# air_pod_case.net
KiCad netlist of a schematic drawn in Altium Designer
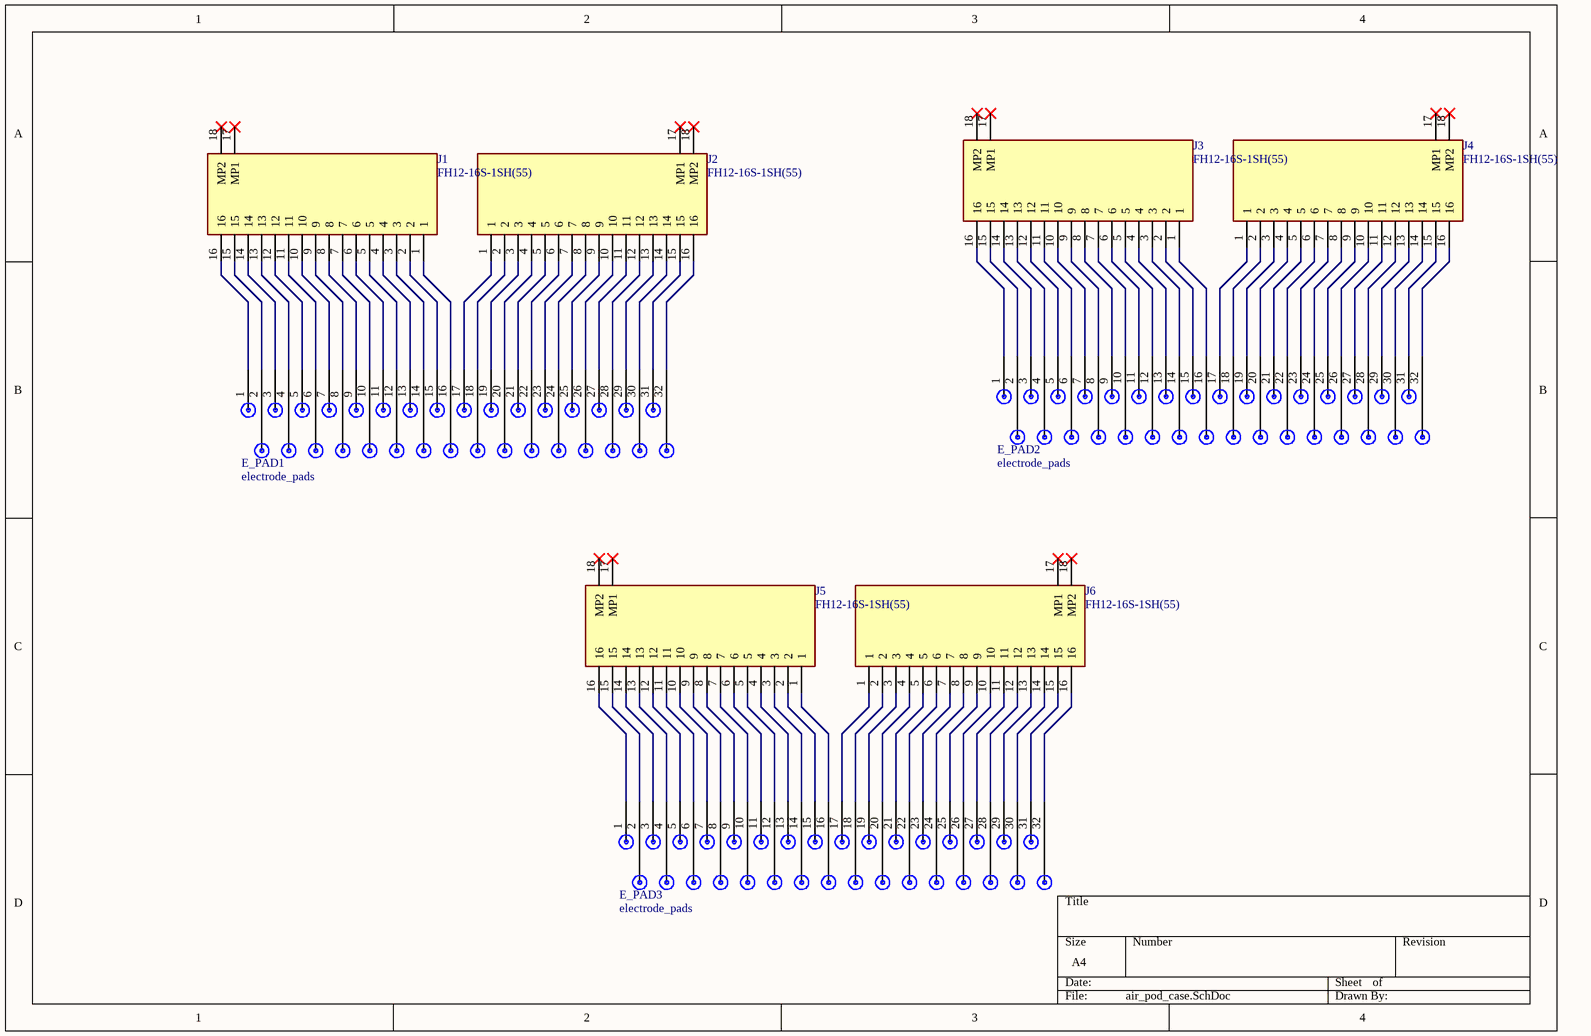
[diagram p0: air_pod_case.SchDoc]

(export (version "E")
  (design (tool "Eeschema 10.0.6"))
  (components
    (comp (ref "E_PAD1")
      (value "electrode_pads")
      (footprint "32_electrode_pads")
      (libsource (lib "32_pads") (part "electrode_pads"))
    )
    (comp (ref "E_PAD2")
      (value "electrode_pads")
      (footprint "32_electrode_pads")
      (libsource (lib "32_pads") (part "electrode_pads"))
    )
    (comp (ref "E_PAD3")
      (value "electrode_pads")
      (footprint "32_electrode_pads")
      (libsource (lib "32_pads") (part "electrode_pads"))
    )
    (comp (ref "J1")
      (value "FH12-16S-1SH(55)")
      (footprint "FH12-16S-1SH(55)")
      (libsource (lib "") (part "FH12-16S-1SH(55)_1"))
    )
    (comp (ref "J2")
      (value "FH12-16S-1SH(55)")
      (footprint "FH12-16S-1SH(55)")
      (libsource (lib "FH12-16S-1SH(55)") (part "FH12-16S-1SH(55)"))
    )
    (comp (ref "J3")
      (value "FH12-16S-1SH(55)")
      (footprint "FH12-16S-1SH(55)")
      (libsource (lib "") (part "FH12-16S-1SH(55)_1"))
    )
    (comp (ref "J4")
      (value "FH12-16S-1SH(55)")
      (footprint "FH12-16S-1SH(55)")
      (libsource (lib "FH12-16S-1SH(55)") (part "FH12-16S-1SH(55)"))
    )
    (comp (ref "J5")
      (value "FH12-16S-1SH(55)")
      (footprint "FH12-16S-1SH(55)")
      (libsource (lib "") (part "FH12-16S-1SH(55)_1"))
    )
    (comp (ref "J6")
      (value "FH12-16S-1SH(55)")
      (footprint "FH12-16S-1SH(55)")
      (libsource (lib "FH12-16S-1SH(55)") (part "FH12-16S-1SH(55)"))
    )
  )
  (nets
    (net (code "1") (name "Net-(E_PAD1-1-Pad2)") (class "Default")
      (node (ref "E_PAD1") (pin "2") (pinfunction "1_2") (pintype "passive"))
      (node (ref "J1") (pin "15") (pinfunction "15_15") (pintype "passive"))
    )
    (net (code "2") (name "Net-(E_PAD1-1-Pad3)") (class "Default")
      (node (ref "E_PAD1") (pin "3") (pinfunction "1_3") (pintype "passive"))
      (node (ref "J1") (pin "14") (pinfunction "14_14") (pintype "passive"))
    )
    (net (code "3") (name "Net-(E_PAD1-1-Pad4)") (class "Default")
      (node (ref "E_PAD1") (pin "4") (pinfunction "1_4") (pintype "passive"))
      (node (ref "J1") (pin "13") (pinfunction "13_13") (pintype "passive"))
    )
    (net (code "4") (name "Net-(E_PAD1-1-Pad5)") (class "Default")
      (node (ref "E_PAD1") (pin "5") (pinfunction "1_5") (pintype "passive"))
      (node (ref "J1") (pin "12") (pinfunction "12_12") (pintype "passive"))
    )
    (net (code "5") (name "Net-(E_PAD1-1-Pad6)") (class "Default")
      (node (ref "E_PAD1") (pin "6") (pinfunction "1_6") (pintype "passive"))
      (node (ref "J1") (pin "11") (pinfunction "11_11") (pintype "passive"))
    )
    (net (code "6") (name "Net-(E_PAD1-1-Pad7)") (class "Default")
      (node (ref "E_PAD1") (pin "7") (pinfunction "1_7") (pintype "passive"))
      (node (ref "J1") (pin "10") (pinfunction "10_10") (pintype "passive"))
    )
    (net (code "7") (name "Net-(E_PAD1-1-Pad8)") (class "Default")
      (node (ref "E_PAD1") (pin "8") (pinfunction "1_8") (pintype "passive"))
      (node (ref "J1") (pin "9") (pinfunction "9_9") (pintype "passive"))
    )
    (net (code "8") (name "Net-(E_PAD1-1-Pad9)") (class "Default")
      (node (ref "E_PAD1") (pin "9") (pinfunction "1_9") (pintype "passive"))
      (node (ref "J1") (pin "8") (pinfunction "8_8") (pintype "passive"))
    )
    (net (code "9") (name "Net-(E_PAD1-1-Pad10)") (class "Default")
      (node (ref "E_PAD1") (pin "10") (pinfunction "1_10") (pintype "passive"))
      (node (ref "J1") (pin "7") (pinfunction "7_7") (pintype "passive"))
    )
    (net (code "10") (name "Net-(E_PAD1-1-Pad11)") (class "Default")
      (node (ref "E_PAD1") (pin "11") (pinfunction "1_11") (pintype "passive"))
      (node (ref "J1") (pin "6") (pinfunction "6_6") (pintype "passive"))
    )
    (net (code "11") (name "Net-(E_PAD1-1-Pad12)") (class "Default")
      (node (ref "E_PAD1") (pin "12") (pinfunction "1_12") (pintype "passive"))
      (node (ref "J1") (pin "5") (pinfunction "5_5") (pintype "passive"))
    )
    (net (code "12") (name "Net-(E_PAD1-1-Pad13)") (class "Default")
      (node (ref "E_PAD1") (pin "13") (pinfunction "1_13") (pintype "passive"))
      (node (ref "J1") (pin "4") (pinfunction "4_4") (pintype "passive"))
    )
    (net (code "13") (name "Net-(E_PAD1-1-Pad14)") (class "Default")
      (node (ref "E_PAD1") (pin "14") (pinfunction "1_14") (pintype "passive"))
      (node (ref "J1") (pin "3") (pinfunction "3_3") (pintype "passive"))
    )
    (net (code "14") (name "Net-(E_PAD1-1-Pad15)") (class "Default")
      (node (ref "E_PAD1") (pin "15") (pinfunction "1_15") (pintype "passive"))
      (node (ref "J1") (pin "2") (pinfunction "2_2") (pintype "passive"))
    )
    (net (code "15") (name "Net-(E_PAD1-1-Pad16)") (class "Default")
      (node (ref "E_PAD1") (pin "16") (pinfunction "1_16") (pintype "passive"))
      (node (ref "J1") (pin "1") (pinfunction "1_1") (pintype "passive"))
    )
    (net (code "16") (name "Net-(E_PAD1-1-Pad17)") (class "Default")
      (node (ref "E_PAD1") (pin "17") (pinfunction "1_17") (pintype "passive"))
      (node (ref "J2") (pin "1") (pinfunction "1_1") (pintype "passive"))
    )
    (net (code "17") (name "Net-(E_PAD1-1-Pad18)") (class "Default")
      (node (ref "E_PAD1") (pin "18") (pinfunction "1_18") (pintype "passive"))
      (node (ref "J2") (pin "2") (pinfunction "2_2") (pintype "passive"))
    )
    (net (code "18") (name "Net-(E_PAD1-1-Pad19)") (class "Default")
      (node (ref "E_PAD1") (pin "19") (pinfunction "1_19") (pintype "passive"))
      (node (ref "J2") (pin "3") (pinfunction "3_3") (pintype "passive"))
    )
    (net (code "19") (name "Net-(E_PAD1-1-Pad20)") (class "Default")
      (node (ref "E_PAD1") (pin "20") (pinfunction "1_20") (pintype "passive"))
      (node (ref "J2") (pin "4") (pinfunction "4_4") (pintype "passive"))
    )
    (net (code "20") (name "Net-(E_PAD1-1-Pad21)") (class "Default")
      (node (ref "E_PAD1") (pin "21") (pinfunction "1_21") (pintype "passive"))
      (node (ref "J2") (pin "5") (pinfunction "5_5") (pintype "passive"))
    )
    (net (code "21") (name "Net-(E_PAD1-1-Pad22)") (class "Default")
      (node (ref "E_PAD1") (pin "22") (pinfunction "1_22") (pintype "passive"))
      (node (ref "J2") (pin "6") (pinfunction "6_6") (pintype "passive"))
    )
    (net (code "22") (name "Net-(E_PAD1-1-Pad23)") (class "Default")
      (node (ref "E_PAD1") (pin "23") (pinfunction "1_23") (pintype "passive"))
      (node (ref "J2") (pin "7") (pinfunction "7_7") (pintype "passive"))
    )
    (net (code "23") (name "Net-(E_PAD1-1-Pad24)") (class "Default")
      (node (ref "E_PAD1") (pin "24") (pinfunction "1_24") (pintype "passive"))
      (node (ref "J2") (pin "8") (pinfunction "8_8") (pintype "passive"))
    )
    (net (code "24") (name "Net-(E_PAD1-1-Pad25)") (class "Default")
      (node (ref "E_PAD1") (pin "25") (pinfunction "1_25") (pintype "passive"))
      (node (ref "J2") (pin "9") (pinfunction "9_9") (pintype "passive"))
    )
    (net (code "25") (name "Net-(E_PAD1-1-Pad26)") (class "Default")
      (node (ref "E_PAD1") (pin "26") (pinfunction "1_26") (pintype "passive"))
      (node (ref "J2") (pin "10") (pinfunction "10_10") (pintype "passive"))
    )
    (net (code "26") (name "Net-(E_PAD1-1-Pad27)") (class "Default")
      (node (ref "E_PAD1") (pin "27") (pinfunction "1_27") (pintype "passive"))
      (node (ref "J2") (pin "11") (pinfunction "11_11") (pintype "passive"))
    )
    (net (code "27") (name "Net-(E_PAD1-1-Pad28)") (class "Default")
      (node (ref "E_PAD1") (pin "28") (pinfunction "1_28") (pintype "passive"))
      (node (ref "J2") (pin "12") (pinfunction "12_12") (pintype "passive"))
    )
    (net (code "28") (name "Net-(E_PAD1-1-Pad29)") (class "Default")
      (node (ref "E_PAD1") (pin "29") (pinfunction "1_29") (pintype "passive"))
      (node (ref "J2") (pin "13") (pinfunction "13_13") (pintype "passive"))
    )
    (net (code "29") (name "Net-(E_PAD1-1-Pad30)") (class "Default")
      (node (ref "E_PAD1") (pin "30") (pinfunction "1_30") (pintype "passive"))
      (node (ref "J2") (pin "14") (pinfunction "14_14") (pintype "passive"))
    )
    (net (code "30") (name "Net-(E_PAD1-1-Pad31)") (class "Default")
      (node (ref "E_PAD1") (pin "31") (pinfunction "1_31") (pintype "passive"))
      (node (ref "J2") (pin "15") (pinfunction "15_15") (pintype "passive"))
    )
    (net (code "31") (name "Net-(E_PAD1-1-Pad32)") (class "Default")
      (node (ref "E_PAD1") (pin "32") (pinfunction "1_32") (pintype "passive"))
      (node (ref "J2") (pin "16") (pinfunction "16_16") (pintype "passive"))
    )
    (net (code "32") (name "Net-(E_PAD1-Pad1)") (class "Default")
      (node (ref "E_PAD1") (pin "1") (pinfunction "1_1") (pintype "passive"))
      (node (ref "J1") (pin "16") (pinfunction "16_16") (pintype "passive"))
    )
    (net (code "33") (name "Net-(E_PAD2-1-Pad2)") (class "Default")
      (node (ref "E_PAD2") (pin "2") (pinfunction "1_2") (pintype "passive"))
      (node (ref "J3") (pin "15") (pinfunction "15_15") (pintype "passive"))
    )
    (net (code "34") (name "Net-(E_PAD2-1-Pad3)") (class "Default")
      (node (ref "E_PAD2") (pin "3") (pinfunction "1_3") (pintype "passive"))
      (node (ref "J3") (pin "14") (pinfunction "14_14") (pintype "passive"))
    )
    (net (code "35") (name "Net-(E_PAD2-1-Pad4)") (class "Default")
      (node (ref "E_PAD2") (pin "4") (pinfunction "1_4") (pintype "passive"))
      (node (ref "J3") (pin "13") (pinfunction "13_13") (pintype "passive"))
    )
    (net (code "36") (name "Net-(E_PAD2-1-Pad5)") (class "Default")
      (node (ref "E_PAD2") (pin "5") (pinfunction "1_5") (pintype "passive"))
      (node (ref "J3") (pin "12") (pinfunction "12_12") (pintype "passive"))
    )
    (net (code "37") (name "Net-(E_PAD2-1-Pad6)") (class "Default")
      (node (ref "E_PAD2") (pin "6") (pinfunction "1_6") (pintype "passive"))
      (node (ref "J3") (pin "11") (pinfunction "11_11") (pintype "passive"))
    )
    (net (code "38") (name "Net-(E_PAD2-1-Pad7)") (class "Default")
      (node (ref "E_PAD2") (pin "7") (pinfunction "1_7") (pintype "passive"))
      (node (ref "J3") (pin "10") (pinfunction "10_10") (pintype "passive"))
    )
    (net (code "39") (name "Net-(E_PAD2-1-Pad8)") (class "Default")
      (node (ref "E_PAD2") (pin "8") (pinfunction "1_8") (pintype "passive"))
      (node (ref "J3") (pin "9") (pinfunction "9_9") (pintype "passive"))
    )
    (net (code "40") (name "Net-(E_PAD2-1-Pad9)") (class "Default")
      (node (ref "E_PAD2") (pin "9") (pinfunction "1_9") (pintype "passive"))
      (node (ref "J3") (pin "8") (pinfunction "8_8") (pintype "passive"))
    )
    (net (code "41") (name "Net-(E_PAD2-1-Pad10)") (class "Default")
      (node (ref "E_PAD2") (pin "10") (pinfunction "1_10") (pintype "passive"))
      (node (ref "J3") (pin "7") (pinfunction "7_7") (pintype "passive"))
    )
    (net (code "42") (name "Net-(E_PAD2-1-Pad11)") (class "Default")
      (node (ref "E_PAD2") (pin "11") (pinfunction "1_11") (pintype "passive"))
      (node (ref "J3") (pin "6") (pinfunction "6_6") (pintype "passive"))
    )
    (net (code "43") (name "Net-(E_PAD2-1-Pad12)") (class "Default")
      (node (ref "E_PAD2") (pin "12") (pinfunction "1_12") (pintype "passive"))
      (node (ref "J3") (pin "5") (pinfunction "5_5") (pintype "passive"))
    )
    (net (code "44") (name "Net-(E_PAD2-1-Pad13)") (class "Default")
      (node (ref "E_PAD2") (pin "13") (pinfunction "1_13") (pintype "passive"))
      (node (ref "J3") (pin "4") (pinfunction "4_4") (pintype "passive"))
    )
    (net (code "45") (name "Net-(E_PAD2-1-Pad14)") (class "Default")
      (node (ref "E_PAD2") (pin "14") (pinfunction "1_14") (pintype "passive"))
      (node (ref "J3") (pin "3") (pinfunction "3_3") (pintype "passive"))
    )
    (net (code "46") (name "Net-(E_PAD2-1-Pad15)") (class "Default")
      (node (ref "E_PAD2") (pin "15") (pinfunction "1_15") (pintype "passive"))
      (node (ref "J3") (pin "2") (pinfunction "2_2") (pintype "passive"))
    )
    (net (code "47") (name "Net-(E_PAD2-1-Pad16)") (class "Default")
      (node (ref "E_PAD2") (pin "16") (pinfunction "1_16") (pintype "passive"))
      (node (ref "J3") (pin "1") (pinfunction "1_1") (pintype "passive"))
    )
    (net (code "48") (name "Net-(E_PAD2-1-Pad17)") (class "Default")
      (node (ref "E_PAD2") (pin "17") (pinfunction "1_17") (pintype "passive"))
      (node (ref "J4") (pin "1") (pinfunction "1_1") (pintype "passive"))
    )
    (net (code "49") (name "Net-(E_PAD2-1-Pad18)") (class "Default")
      (node (ref "E_PAD2") (pin "18") (pinfunction "1_18") (pintype "passive"))
      (node (ref "J4") (pin "2") (pinfunction "2_2") (pintype "passive"))
    )
    (net (code "50") (name "Net-(E_PAD2-1-Pad19)") (class "Default")
      (node (ref "E_PAD2") (pin "19") (pinfunction "1_19") (pintype "passive"))
      (node (ref "J4") (pin "3") (pinfunction "3_3") (pintype "passive"))
    )
    (net (code "51") (name "Net-(E_PAD2-1-Pad20)") (class "Default")
      (node (ref "E_PAD2") (pin "20") (pinfunction "1_20") (pintype "passive"))
      (node (ref "J4") (pin "4") (pinfunction "4_4") (pintype "passive"))
    )
    (net (code "52") (name "Net-(E_PAD2-1-Pad21)") (class "Default")
      (node (ref "E_PAD2") (pin "21") (pinfunction "1_21") (pintype "passive"))
      (node (ref "J4") (pin "5") (pinfunction "5_5") (pintype "passive"))
    )
    (net (code "53") (name "Net-(E_PAD2-1-Pad22)") (class "Default")
      (node (ref "E_PAD2") (pin "22") (pinfunction "1_22") (pintype "passive"))
      (node (ref "J4") (pin "6") (pinfunction "6_6") (pintype "passive"))
    )
    (net (code "54") (name "Net-(E_PAD2-1-Pad23)") (class "Default")
      (node (ref "E_PAD2") (pin "23") (pinfunction "1_23") (pintype "passive"))
      (node (ref "J4") (pin "7") (pinfunction "7_7") (pintype "passive"))
    )
    (net (code "55") (name "Net-(E_PAD2-1-Pad24)") (class "Default")
      (node (ref "E_PAD2") (pin "24") (pinfunction "1_24") (pintype "passive"))
      (node (ref "J4") (pin "8") (pinfunction "8_8") (pintype "passive"))
    )
    (net (code "56") (name "Net-(E_PAD2-1-Pad25)") (class "Default")
      (node (ref "E_PAD2") (pin "25") (pinfunction "1_25") (pintype "passive"))
      (node (ref "J4") (pin "9") (pinfunction "9_9") (pintype "passive"))
    )
    (net (code "57") (name "Net-(E_PAD2-1-Pad26)") (class "Default")
      (node (ref "E_PAD2") (pin "26") (pinfunction "1_26") (pintype "passive"))
      (node (ref "J4") (pin "10") (pinfunction "10_10") (pintype "passive"))
    )
    (net (code "58") (name "Net-(E_PAD2-1-Pad27)") (class "Default")
      (node (ref "E_PAD2") (pin "27") (pinfunction "1_27") (pintype "passive"))
      (node (ref "J4") (pin "11") (pinfunction "11_11") (pintype "passive"))
    )
    (net (code "59") (name "Net-(E_PAD2-1-Pad28)") (class "Default")
      (node (ref "E_PAD2") (pin "28") (pinfunction "1_28") (pintype "passive"))
      (node (ref "J4") (pin "12") (pinfunction "12_12") (pintype "passive"))
    )
    (net (code "60") (name "Net-(E_PAD2-1-Pad29)") (class "Default")
      (node (ref "E_PAD2") (pin "29") (pinfunction "1_29") (pintype "passive"))
      (node (ref "J4") (pin "13") (pinfunction "13_13") (pintype "passive"))
    )
    (net (code "61") (name "Net-(E_PAD2-1-Pad30)") (class "Default")
      (node (ref "E_PAD2") (pin "30") (pinfunction "1_30") (pintype "passive"))
      (node (ref "J4") (pin "14") (pinfunction "14_14") (pintype "passive"))
    )
    (net (code "62") (name "Net-(E_PAD2-1-Pad31)") (class "Default")
      (node (ref "E_PAD2") (pin "31") (pinfunction "1_31") (pintype "passive"))
      (node (ref "J4") (pin "15") (pinfunction "15_15") (pintype "passive"))
    )
    (net (code "63") (name "Net-(E_PAD2-1-Pad32)") (class "Default")
      (node (ref "E_PAD2") (pin "32") (pinfunction "1_32") (pintype "passive"))
      (node (ref "J4") (pin "16") (pinfunction "16_16") (pintype "passive"))
    )
    (net (code "64") (name "Net-(E_PAD2-Pad1)") (class "Default")
      (node (ref "E_PAD2") (pin "1") (pinfunction "1_1") (pintype "passive"))
      (node (ref "J3") (pin "16") (pinfunction "16_16") (pintype "passive"))
    )
    (net (code "65") (name "Net-(E_PAD3-1-Pad2)") (class "Default")
      (node (ref "E_PAD3") (pin "2") (pinfunction "1_2") (pintype "passive"))
      (node (ref "J5") (pin "15") (pinfunction "15_15") (pintype "passive"))
    )
    (net (code "66") (name "Net-(E_PAD3-1-Pad3)") (class "Default")
      (node (ref "E_PAD3") (pin "3") (pinfunction "1_3") (pintype "passive"))
      (node (ref "J5") (pin "14") (pinfunction "14_14") (pintype "passive"))
    )
    (net (code "67") (name "Net-(E_PAD3-1-Pad4)") (class "Default")
      (node (ref "E_PAD3") (pin "4") (pinfunction "1_4") (pintype "passive"))
      (node (ref "J5") (pin "13") (pinfunction "13_13") (pintype "passive"))
    )
    (net (code "68") (name "Net-(E_PAD3-1-Pad5)") (class "Default")
      (node (ref "E_PAD3") (pin "5") (pinfunction "1_5") (pintype "passive"))
      (node (ref "J5") (pin "12") (pinfunction "12_12") (pintype "passive"))
    )
    (net (code "69") (name "Net-(E_PAD3-1-Pad6)") (class "Default")
      (node (ref "E_PAD3") (pin "6") (pinfunction "1_6") (pintype "passive"))
      (node (ref "J5") (pin "11") (pinfunction "11_11") (pintype "passive"))
    )
    (net (code "70") (name "Net-(E_PAD3-1-Pad7)") (class "Default")
      (node (ref "E_PAD3") (pin "7") (pinfunction "1_7") (pintype "passive"))
      (node (ref "J5") (pin "10") (pinfunction "10_10") (pintype "passive"))
    )
    (net (code "71") (name "Net-(E_PAD3-1-Pad8)") (class "Default")
      (node (ref "E_PAD3") (pin "8") (pinfunction "1_8") (pintype "passive"))
      (node (ref "J5") (pin "9") (pinfunction "9_9") (pintype "passive"))
    )
    (net (code "72") (name "Net-(E_PAD3-1-Pad9)") (class "Default")
      (node (ref "E_PAD3") (pin "9") (pinfunction "1_9") (pintype "passive"))
      (node (ref "J5") (pin "8") (pinfunction "8_8") (pintype "passive"))
    )
    (net (code "73") (name "Net-(E_PAD3-1-Pad10)") (class "Default")
      (node (ref "E_PAD3") (pin "10") (pinfunction "1_10") (pintype "passive"))
      (node (ref "J5") (pin "7") (pinfunction "7_7") (pintype "passive"))
    )
    (net (code "74") (name "Net-(E_PAD3-1-Pad11)") (class "Default")
      (node (ref "E_PAD3") (pin "11") (pinfunction "1_11") (pintype "passive"))
      (node (ref "J5") (pin "6") (pinfunction "6_6") (pintype "passive"))
    )
    (net (code "75") (name "Net-(E_PAD3-1-Pad12)") (class "Default")
      (node (ref "E_PAD3") (pin "12") (pinfunction "1_12") (pintype "passive"))
      (node (ref "J5") (pin "5") (pinfunction "5_5") (pintype "passive"))
    )
    (net (code "76") (name "Net-(E_PAD3-1-Pad13)") (class "Default")
      (node (ref "E_PAD3") (pin "13") (pinfunction "1_13") (pintype "passive"))
      (node (ref "J5") (pin "4") (pinfunction "4_4") (pintype "passive"))
    )
    (net (code "77") (name "Net-(E_PAD3-1-Pad14)") (class "Default")
      (node (ref "E_PAD3") (pin "14") (pinfunction "1_14") (pintype "passive"))
      (node (ref "J5") (pin "3") (pinfunction "3_3") (pintype "passive"))
    )
    (net (code "78") (name "Net-(E_PAD3-1-Pad15)") (class "Default")
      (node (ref "E_PAD3") (pin "15") (pinfunction "1_15") (pintype "passive"))
      (node (ref "J5") (pin "2") (pinfunction "2_2") (pintype "passive"))
    )
    (net (code "79") (name "Net-(E_PAD3-1-Pad16)") (class "Default")
      (node (ref "E_PAD3") (pin "16") (pinfunction "1_16") (pintype "passive"))
      (node (ref "J5") (pin "1") (pinfunction "1_1") (pintype "passive"))
    )
    (net (code "80") (name "Net-(E_PAD3-1-Pad17)") (class "Default")
      (node (ref "E_PAD3") (pin "17") (pinfunction "1_17") (pintype "passive"))
      (node (ref "J6") (pin "1") (pinfunction "1_1") (pintype "passive"))
    )
    (net (code "81") (name "Net-(E_PAD3-1-Pad18)") (class "Default")
      (node (ref "E_PAD3") (pin "18") (pinfunction "1_18") (pintype "passive"))
      (node (ref "J6") (pin "2") (pinfunction "2_2") (pintype "passive"))
    )
    (net (code "82") (name "Net-(E_PAD3-1-Pad19)") (class "Default")
      (node (ref "E_PAD3") (pin "19") (pinfunction "1_19") (pintype "passive"))
      (node (ref "J6") (pin "3") (pinfunction "3_3") (pintype "passive"))
    )
    (net (code "83") (name "Net-(E_PAD3-1-Pad20)") (class "Default")
      (node (ref "E_PAD3") (pin "20") (pinfunction "1_20") (pintype "passive"))
      (node (ref "J6") (pin "4") (pinfunction "4_4") (pintype "passive"))
    )
    (net (code "84") (name "Net-(E_PAD3-1-Pad21)") (class "Default")
      (node (ref "E_PAD3") (pin "21") (pinfunction "1_21") (pintype "passive"))
      (node (ref "J6") (pin "5") (pinfunction "5_5") (pintype "passive"))
    )
    (net (code "85") (name "Net-(E_PAD3-1-Pad22)") (class "Default")
      (node (ref "E_PAD3") (pin "22") (pinfunction "1_22") (pintype "passive"))
      (node (ref "J6") (pin "6") (pinfunction "6_6") (pintype "passive"))
    )
    (net (code "86") (name "Net-(E_PAD3-1-Pad23)") (class "Default")
      (node (ref "E_PAD3") (pin "23") (pinfunction "1_23") (pintype "passive"))
      (node (ref "J6") (pin "7") (pinfunction "7_7") (pintype "passive"))
    )
    (net (code "87") (name "Net-(E_PAD3-1-Pad24)") (class "Default")
      (node (ref "E_PAD3") (pin "24") (pinfunction "1_24") (pintype "passive"))
      (node (ref "J6") (pin "8") (pinfunction "8_8") (pintype "passive"))
    )
    (net (code "88") (name "Net-(E_PAD3-1-Pad25)") (class "Default")
      (node (ref "E_PAD3") (pin "25") (pinfunction "1_25") (pintype "passive"))
      (node (ref "J6") (pin "9") (pinfunction "9_9") (pintype "passive"))
    )
    (net (code "89") (name "Net-(E_PAD3-1-Pad26)") (class "Default")
      (node (ref "E_PAD3") (pin "26") (pinfunction "1_26") (pintype "passive"))
      (node (ref "J6") (pin "10") (pinfunction "10_10") (pintype "passive"))
    )
    (net (code "90") (name "Net-(E_PAD3-1-Pad27)") (class "Default")
      (node (ref "E_PAD3") (pin "27") (pinfunction "1_27") (pintype "passive"))
      (node (ref "J6") (pin "11") (pinfunction "11_11") (pintype "passive"))
    )
    (net (code "91") (name "Net-(E_PAD3-1-Pad28)") (class "Default")
      (node (ref "E_PAD3") (pin "28") (pinfunction "1_28") (pintype "passive"))
      (node (ref "J6") (pin "12") (pinfunction "12_12") (pintype "passive"))
    )
    (net (code "92") (name "Net-(E_PAD3-1-Pad29)") (class "Default")
      (node (ref "E_PAD3") (pin "29") (pinfunction "1_29") (pintype "passive"))
      (node (ref "J6") (pin "13") (pinfunction "13_13") (pintype "passive"))
    )
    (net (code "93") (name "Net-(E_PAD3-1-Pad30)") (class "Default")
      (node (ref "E_PAD3") (pin "30") (pinfunction "1_30") (pintype "passive"))
      (node (ref "J6") (pin "14") (pinfunction "14_14") (pintype "passive"))
    )
    (net (code "94") (name "Net-(E_PAD3-1-Pad31)") (class "Default")
      (node (ref "E_PAD3") (pin "31") (pinfunction "1_31") (pintype "passive"))
      (node (ref "J6") (pin "15") (pinfunction "15_15") (pintype "passive"))
    )
    (net (code "95") (name "Net-(E_PAD3-1-Pad32)") (class "Default")
      (node (ref "E_PAD3") (pin "32") (pinfunction "1_32") (pintype "passive"))
      (node (ref "J6") (pin "16") (pinfunction "16_16") (pintype "passive"))
    )
    (net (code "96") (name "Net-(E_PAD3-Pad1)") (class "Default")
      (node (ref "E_PAD3") (pin "1") (pinfunction "1_1") (pintype "passive"))
      (node (ref "J5") (pin "16") (pinfunction "16_16") (pintype "passive"))
    )
    (net (code "97") (name "unconnected-(J1-MP1-Pad17)") (class "Default")
      (node (ref "J1") (pin "17") (pinfunction "MP1_17") (pintype "passive+no_connect"))
    )
    (net (code "98") (name "unconnected-(J1-MP2-Pad18)") (class "Default")
      (node (ref "J1") (pin "18") (pinfunction "MP2_18") (pintype "passive+no_connect"))
    )
    (net (code "99") (name "unconnected-(J2-MP1-Pad17)") (class "Default")
      (node (ref "J2") (pin "17") (pinfunction "MP1_17") (pintype "passive+no_connect"))
    )
    (net (code "100") (name "unconnected-(J2-MP2-Pad18)") (class "Default")
      (node (ref "J2") (pin "18") (pinfunction "MP2_18") (pintype "passive+no_connect"))
    )
    (net (code "101") (name "unconnected-(J3-MP1-Pad17)") (class "Default")
      (node (ref "J3") (pin "17") (pinfunction "MP1_17") (pintype "passive+no_connect"))
    )
    (net (code "102") (name "unconnected-(J3-MP2-Pad18)") (class "Default")
      (node (ref "J3") (pin "18") (pinfunction "MP2_18") (pintype "passive+no_connect"))
    )
    (net (code "103") (name "unconnected-(J4-MP1-Pad17)") (class "Default")
      (node (ref "J4") (pin "17") (pinfunction "MP1_17") (pintype "passive+no_connect"))
    )
    (net (code "104") (name "unconnected-(J4-MP2-Pad18)") (class "Default")
      (node (ref "J4") (pin "18") (pinfunction "MP2_18") (pintype "passive+no_connect"))
    )
    (net (code "105") (name "unconnected-(J5-MP1-Pad17)") (class "Default")
      (node (ref "J5") (pin "17") (pinfunction "MP1_17") (pintype "passive+no_connect"))
    )
    (net (code "106") (name "unconnected-(J5-MP2-Pad18)") (class "Default")
      (node (ref "J5") (pin "18") (pinfunction "MP2_18") (pintype "passive+no_connect"))
    )
    (net (code "107") (name "unconnected-(J6-MP1-Pad17)") (class "Default")
      (node (ref "J6") (pin "17") (pinfunction "MP1_17") (pintype "passive+no_connect"))
    )
    (net (code "108") (name "unconnected-(J6-MP2-Pad18)") (class "Default")
      (node (ref "J6") (pin "18") (pinfunction "MP2_18") (pintype "passive+no_connect"))
    )
  )
)
